# MDR50-Breakout.net
KiCad netlist of a schematic drawn in EAGLE
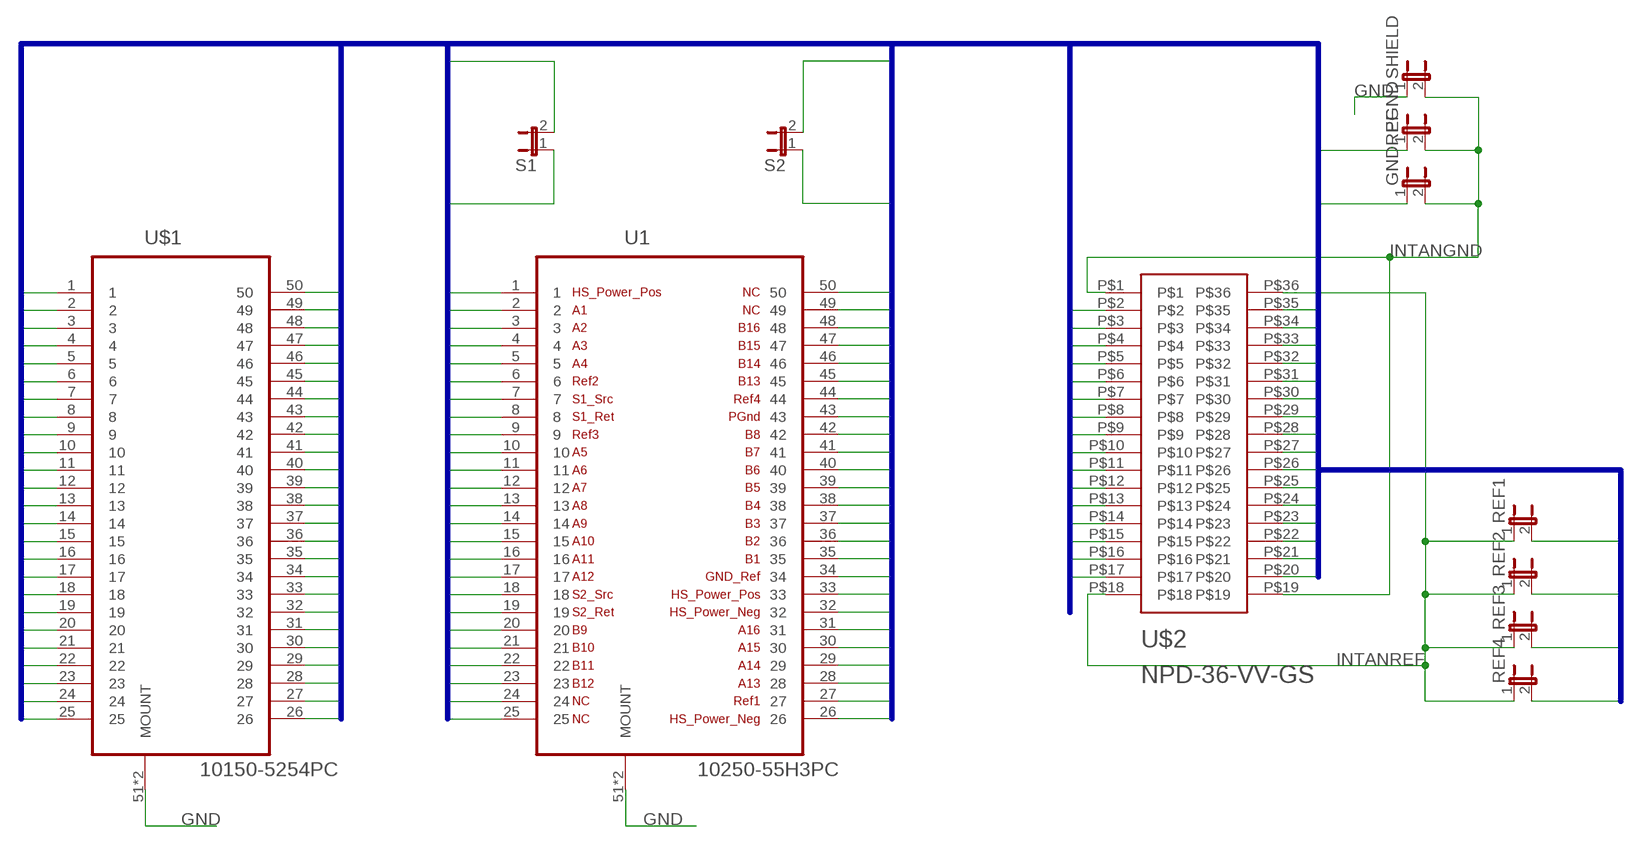
[diagram p0: schematic, sheet 1]

(export (version "E")
  (design (tool "Eeschema 10.0.6"))
  (components
    (comp (ref "GNDREF")
      (value "JUMPER-2PTH")
      (footprint "eagle-import:1X02")
      (libsource (lib "eagle-import") (part "JUMPER-2PTH"))
    )
    (comp (ref "PGND")
      (value "JUMPER-2PTH")
      (footprint "eagle-import:1X02")
      (libsource (lib "eagle-import") (part "JUMPER-2PTH"))
    )
    (comp (ref "REF1")
      (value "JUMPER-2PTH")
      (footprint "eagle-import:1X02")
      (libsource (lib "eagle-import") (part "JUMPER-2PTH"))
    )
    (comp (ref "REF2")
      (value "JUMPER-2PTH")
      (footprint "eagle-import:1X02")
      (libsource (lib "eagle-import") (part "JUMPER-2PTH"))
    )
    (comp (ref "REF3")
      (value "JUMPER-2PTH")
      (footprint "eagle-import:1X02")
      (libsource (lib "eagle-import") (part "JUMPER-2PTH"))
    )
    (comp (ref "REF4")
      (value "JUMPER-2PTH")
      (footprint "eagle-import:1X02")
      (libsource (lib "eagle-import") (part "JUMPER-2PTH"))
    )
    (comp (ref "S1")
      (value "JUMPER-2PTH")
      (footprint "eagle-import:1X02")
      (libsource (lib "eagle-import") (part "JUMPER-2PTH"))
    )
    (comp (ref "S2")
      (value "JUMPER-2PTH")
      (footprint "eagle-import:1X02")
      (libsource (lib "eagle-import") (part "JUMPER-2PTH"))
    )
    (comp (ref "SHIELD")
      (value "JUMPER-2PTH")
      (footprint "eagle-import:1X02")
      (libsource (lib "eagle-import") (part "JUMPER-2PTH"))
    )
    (comp (ref "U$1")
      (value "10150-5254PC")
      (footprint "eagle-import:3M_10150-5242PC")
      (libsource (lib "eagle-import") (part "10150-5254PC"))
    )
    (comp (ref "U$2")
      (value "NPD-36-VV-GS")
      (footprint "eagle-import:NPD-36-VV-GS")
      (libsource (lib "eagle-import") (part "NPD-36-VV-GS"))
    )
    (comp (ref "U1")
      (value "10250-55H3PC")
      (footprint "eagle-import:3M_10250-55H3PC")
      (libsource (lib "eagle-import") (part "10250-55H3PC"))
    )
  )
  (nets
    (net (code "1") (name "/D1") (class "Default")
      (node (ref "U$1") (pin "1") (pinfunction "1_1") (pintype "passive"))
      (node (ref "U1") (pin "1") (pinfunction "1_1") (pintype "passive"))
    )
    (net (code "2") (name "/D2") (class "Default")
      (node (ref "U$1") (pin "2") (pinfunction "2_2") (pintype "passive"))
      (node (ref "U$2") (pin "P$10") (pinfunction "P$10_P$10") (pintype "bidirectional"))
      (node (ref "U1") (pin "2") (pinfunction "2_2") (pintype "passive"))
    )
    (net (code "3") (name "/D3") (class "Default")
      (node (ref "U$1") (pin "3") (pinfunction "3_3") (pintype "passive"))
      (node (ref "U$2") (pin "P$11") (pinfunction "P$11_P$11") (pintype "bidirectional"))
      (node (ref "U1") (pin "3") (pinfunction "3_3") (pintype "passive"))
    )
    (net (code "4") (name "/D4") (class "Default")
      (node (ref "U$1") (pin "4") (pinfunction "4_4") (pintype "passive"))
      (node (ref "U$2") (pin "P$12") (pinfunction "P$12_P$12") (pintype "bidirectional"))
      (node (ref "U1") (pin "4") (pinfunction "4_4") (pintype "passive"))
    )
    (net (code "5") (name "/D5") (class "Default")
      (node (ref "U$1") (pin "5") (pinfunction "5_5") (pintype "passive"))
      (node (ref "U$2") (pin "P$13") (pinfunction "P$13_P$13") (pintype "bidirectional"))
      (node (ref "U1") (pin "5") (pinfunction "5_5") (pintype "passive"))
    )
    (net (code "6") (name "/D6") (class "Default")
      (node (ref "REF2") (pin "2") (pinfunction "2_2") (pintype "passive"))
      (node (ref "U$1") (pin "6") (pinfunction "6_6") (pintype "passive"))
      (node (ref "U1") (pin "6") (pinfunction "6_6") (pintype "passive"))
    )
    (net (code "7") (name "/D7") (class "Default")
      (node (ref "S1") (pin "1") (pinfunction "1_1") (pintype "passive"))
      (node (ref "U$1") (pin "7") (pinfunction "7_7") (pintype "passive"))
      (node (ref "U1") (pin "7") (pinfunction "7_7") (pintype "passive"))
    )
    (net (code "8") (name "/D8") (class "Default")
      (node (ref "S1") (pin "2") (pinfunction "2_2") (pintype "passive"))
      (node (ref "U$1") (pin "8") (pinfunction "8_8") (pintype "passive"))
      (node (ref "U1") (pin "8") (pinfunction "8_8") (pintype "passive"))
    )
    (net (code "9") (name "/D9") (class "Default")
      (node (ref "REF3") (pin "2") (pinfunction "2_2") (pintype "passive"))
      (node (ref "U$1") (pin "9") (pinfunction "9_9") (pintype "passive"))
      (node (ref "U1") (pin "9") (pinfunction "9_9") (pintype "passive"))
    )
    (net (code "10") (name "/D10") (class "Default")
      (node (ref "U$1") (pin "10") (pinfunction "10_10") (pintype "passive"))
      (node (ref "U$2") (pin "P$14") (pinfunction "P$14_P$14") (pintype "bidirectional"))
      (node (ref "U1") (pin "10") (pinfunction "10_10") (pintype "passive"))
    )
    (net (code "11") (name "/D11") (class "Default")
      (node (ref "U$1") (pin "11") (pinfunction "11_11") (pintype "passive"))
      (node (ref "U$2") (pin "P$15") (pinfunction "P$15_P$15") (pintype "bidirectional"))
      (node (ref "U1") (pin "11") (pinfunction "11_11") (pintype "passive"))
    )
    (net (code "12") (name "/D12") (class "Default")
      (node (ref "U$1") (pin "12") (pinfunction "12_12") (pintype "passive"))
      (node (ref "U$2") (pin "P$16") (pinfunction "P$16_P$16") (pintype "bidirectional"))
      (node (ref "U1") (pin "12") (pinfunction "12_12") (pintype "passive"))
    )
    (net (code "13") (name "/D13") (class "Default")
      (node (ref "U$1") (pin "13") (pinfunction "13_13") (pintype "passive"))
      (node (ref "U$2") (pin "P$17") (pinfunction "P$17_P$17") (pintype "bidirectional"))
      (node (ref "U1") (pin "13") (pinfunction "13_13") (pintype "passive"))
    )
    (net (code "14") (name "/D14") (class "Default")
      (node (ref "U$1") (pin "14") (pinfunction "14_14") (pintype "passive"))
      (node (ref "U$2") (pin "P$20") (pinfunction "P$20_P$20") (pintype "bidirectional"))
      (node (ref "U1") (pin "14") (pinfunction "14_14") (pintype "passive"))
    )
    (net (code "15") (name "/D15") (class "Default")
      (node (ref "U$1") (pin "15") (pinfunction "15_15") (pintype "passive"))
      (node (ref "U$2") (pin "P$21") (pinfunction "P$21_P$21") (pintype "bidirectional"))
      (node (ref "U1") (pin "15") (pinfunction "15_15") (pintype "passive"))
    )
    (net (code "16") (name "/D16") (class "Default")
      (node (ref "U$1") (pin "16") (pinfunction "16_16") (pintype "passive"))
      (node (ref "U$2") (pin "P$22") (pinfunction "P$22_P$22") (pintype "bidirectional"))
      (node (ref "U1") (pin "16") (pinfunction "16_16") (pintype "passive"))
    )
    (net (code "17") (name "/D17") (class "Default")
      (node (ref "U$1") (pin "17") (pinfunction "17_17") (pintype "passive"))
      (node (ref "U$2") (pin "P$23") (pinfunction "P$23_P$23") (pintype "bidirectional"))
      (node (ref "U1") (pin "17") (pinfunction "17_17") (pintype "passive"))
    )
    (net (code "18") (name "/D18") (class "Default")
      (node (ref "S2") (pin "1") (pinfunction "1_1") (pintype "passive"))
      (node (ref "U$1") (pin "18") (pinfunction "18_18") (pintype "passive"))
      (node (ref "U1") (pin "18") (pinfunction "18_18") (pintype "passive"))
    )
    (net (code "19") (name "/D19") (class "Default")
      (node (ref "S2") (pin "2") (pinfunction "2_2") (pintype "passive"))
      (node (ref "U$1") (pin "19") (pinfunction "19_19") (pintype "passive"))
      (node (ref "U1") (pin "19") (pinfunction "19_19") (pintype "passive"))
    )
    (net (code "20") (name "/D20") (class "Default")
      (node (ref "U$1") (pin "20") (pinfunction "20_20") (pintype "passive"))
      (node (ref "U$2") (pin "P$2") (pinfunction "P$2_P$2") (pintype "bidirectional"))
      (node (ref "U1") (pin "20") (pinfunction "20_20") (pintype "passive"))
    )
    (net (code "21") (name "/D21") (class "Default")
      (node (ref "U$1") (pin "21") (pinfunction "21_21") (pintype "passive"))
      (node (ref "U$2") (pin "P$3") (pinfunction "P$3_P$3") (pintype "bidirectional"))
      (node (ref "U1") (pin "21") (pinfunction "21_21") (pintype "passive"))
    )
    (net (code "22") (name "/D22") (class "Default")
      (node (ref "U$1") (pin "22") (pinfunction "22_22") (pintype "passive"))
      (node (ref "U$2") (pin "P$4") (pinfunction "P$4_P$4") (pintype "bidirectional"))
      (node (ref "U1") (pin "22") (pinfunction "22_22") (pintype "passive"))
    )
    (net (code "23") (name "/D23") (class "Default")
      (node (ref "U$1") (pin "23") (pinfunction "23_23") (pintype "passive"))
      (node (ref "U$2") (pin "P$5") (pinfunction "P$5_P$5") (pintype "bidirectional"))
      (node (ref "U1") (pin "23") (pinfunction "23_23") (pintype "passive"))
    )
    (net (code "24") (name "/D24") (class "Default")
      (node (ref "U$1") (pin "24") (pinfunction "24_24") (pintype "passive"))
      (node (ref "U1") (pin "24") (pinfunction "24_24") (pintype "passive"))
    )
    (net (code "25") (name "/D25") (class "Default")
      (node (ref "U$1") (pin "25") (pinfunction "25_25") (pintype "passive"))
      (node (ref "U1") (pin "25") (pinfunction "25_25") (pintype "passive"))
    )
    (net (code "26") (name "/D26") (class "Default")
      (node (ref "U$1") (pin "26") (pinfunction "26_26") (pintype "passive"))
      (node (ref "U1") (pin "26") (pinfunction "26_26") (pintype "passive"))
    )
    (net (code "27") (name "/D27") (class "Default")
      (node (ref "REF1") (pin "2") (pinfunction "2_2") (pintype "passive"))
      (node (ref "U$1") (pin "27") (pinfunction "27_27") (pintype "passive"))
      (node (ref "U1") (pin "27") (pinfunction "27_27") (pintype "passive"))
    )
    (net (code "28") (name "/D28") (class "Default")
      (node (ref "U$1") (pin "28") (pinfunction "28_28") (pintype "passive"))
      (node (ref "U$2") (pin "P$24") (pinfunction "P$24_P$24") (pintype "bidirectional"))
      (node (ref "U1") (pin "28") (pinfunction "28_28") (pintype "passive"))
    )
    (net (code "29") (name "/D29") (class "Default")
      (node (ref "U$1") (pin "29") (pinfunction "29_29") (pintype "passive"))
      (node (ref "U$2") (pin "P$25") (pinfunction "P$25_P$25") (pintype "bidirectional"))
      (node (ref "U1") (pin "29") (pinfunction "29_29") (pintype "passive"))
    )
    (net (code "30") (name "/D30") (class "Default")
      (node (ref "U$1") (pin "30") (pinfunction "30_30") (pintype "passive"))
      (node (ref "U$2") (pin "P$26") (pinfunction "P$26_P$26") (pintype "bidirectional"))
      (node (ref "U1") (pin "30") (pinfunction "30_30") (pintype "passive"))
    )
    (net (code "31") (name "/D31") (class "Default")
      (node (ref "U$1") (pin "31") (pinfunction "31_31") (pintype "passive"))
      (node (ref "U$2") (pin "P$27") (pinfunction "P$27_P$27") (pintype "bidirectional"))
      (node (ref "U1") (pin "31") (pinfunction "31_31") (pintype "passive"))
    )
    (net (code "32") (name "/D32") (class "Default")
      (node (ref "U$1") (pin "32") (pinfunction "32_32") (pintype "passive"))
      (node (ref "U1") (pin "32") (pinfunction "32_32") (pintype "passive"))
    )
    (net (code "33") (name "/D33") (class "Default")
      (node (ref "U$1") (pin "33") (pinfunction "33_33") (pintype "passive"))
      (node (ref "U1") (pin "33") (pinfunction "33_33") (pintype "passive"))
    )
    (net (code "34") (name "/D34") (class "Default")
      (node (ref "GNDREF") (pin "1") (pinfunction "1_1") (pintype "passive"))
      (node (ref "U$1") (pin "34") (pinfunction "34_34") (pintype "passive"))
      (node (ref "U1") (pin "34") (pinfunction "34_34") (pintype "passive"))
    )
    (net (code "35") (name "/D35") (class "Default")
      (node (ref "U$1") (pin "35") (pinfunction "35_35") (pintype "passive"))
      (node (ref "U$2") (pin "P$28") (pinfunction "P$28_P$28") (pintype "bidirectional"))
      (node (ref "U1") (pin "35") (pinfunction "35_35") (pintype "passive"))
    )
    (net (code "36") (name "/D36") (class "Default")
      (node (ref "U$1") (pin "36") (pinfunction "36_36") (pintype "passive"))
      (node (ref "U$2") (pin "P$29") (pinfunction "P$29_P$29") (pintype "bidirectional"))
      (node (ref "U1") (pin "36") (pinfunction "36_36") (pintype "passive"))
    )
    (net (code "37") (name "/D37") (class "Default")
      (node (ref "U$1") (pin "37") (pinfunction "37_37") (pintype "passive"))
      (node (ref "U$2") (pin "P$30") (pinfunction "P$30_P$30") (pintype "bidirectional"))
      (node (ref "U1") (pin "37") (pinfunction "37_37") (pintype "passive"))
    )
    (net (code "38") (name "/D38") (class "Default")
      (node (ref "U$1") (pin "38") (pinfunction "38_38") (pintype "passive"))
      (node (ref "U$2") (pin "P$31") (pinfunction "P$31_P$31") (pintype "bidirectional"))
      (node (ref "U1") (pin "38") (pinfunction "38_38") (pintype "passive"))
    )
    (net (code "39") (name "/D39") (class "Default")
      (node (ref "U$1") (pin "39") (pinfunction "39_39") (pintype "passive"))
      (node (ref "U$2") (pin "P$32") (pinfunction "P$32_P$32") (pintype "bidirectional"))
      (node (ref "U1") (pin "39") (pinfunction "39_39") (pintype "passive"))
    )
    (net (code "40") (name "/D40") (class "Default")
      (node (ref "U$1") (pin "40") (pinfunction "40_40") (pintype "passive"))
      (node (ref "U$2") (pin "P$33") (pinfunction "P$33_P$33") (pintype "bidirectional"))
      (node (ref "U1") (pin "40") (pinfunction "40_40") (pintype "passive"))
    )
    (net (code "41") (name "/D41") (class "Default")
      (node (ref "U$1") (pin "41") (pinfunction "41_41") (pintype "passive"))
      (node (ref "U$2") (pin "P$34") (pinfunction "P$34_P$34") (pintype "bidirectional"))
      (node (ref "U1") (pin "41") (pinfunction "41_41") (pintype "passive"))
    )
    (net (code "42") (name "/D42") (class "Default")
      (node (ref "U$1") (pin "42") (pinfunction "42_42") (pintype "passive"))
      (node (ref "U$2") (pin "P$35") (pinfunction "P$35_P$35") (pintype "bidirectional"))
      (node (ref "U1") (pin "42") (pinfunction "42_42") (pintype "passive"))
    )
    (net (code "43") (name "/D43") (class "Default")
      (node (ref "PGND") (pin "1") (pinfunction "1_1") (pintype "passive"))
      (node (ref "U$1") (pin "43") (pinfunction "43_43") (pintype "passive"))
      (node (ref "U1") (pin "43") (pinfunction "43_43") (pintype "passive"))
    )
    (net (code "44") (name "/D44") (class "Default")
      (node (ref "REF4") (pin "2") (pinfunction "2_2") (pintype "passive"))
      (node (ref "U$1") (pin "44") (pinfunction "44_44") (pintype "passive"))
      (node (ref "U1") (pin "44") (pinfunction "44_44") (pintype "passive"))
    )
    (net (code "45") (name "/D45") (class "Default")
      (node (ref "U$1") (pin "45") (pinfunction "45_45") (pintype "passive"))
      (node (ref "U$2") (pin "P$6") (pinfunction "P$6_P$6") (pintype "bidirectional"))
      (node (ref "U1") (pin "45") (pinfunction "45_45") (pintype "passive"))
    )
    (net (code "46") (name "/D46") (class "Default")
      (node (ref "U$1") (pin "46") (pinfunction "46_46") (pintype "passive"))
      (node (ref "U$2") (pin "P$7") (pinfunction "P$7_P$7") (pintype "bidirectional"))
      (node (ref "U1") (pin "46") (pinfunction "46_46") (pintype "passive"))
    )
    (net (code "47") (name "/D47") (class "Default")
      (node (ref "U$1") (pin "47") (pinfunction "47_47") (pintype "passive"))
      (node (ref "U$2") (pin "P$8") (pinfunction "P$8_P$8") (pintype "bidirectional"))
      (node (ref "U1") (pin "47") (pinfunction "47_47") (pintype "passive"))
    )
    (net (code "48") (name "/D48") (class "Default")
      (node (ref "U$1") (pin "48") (pinfunction "48_48") (pintype "passive"))
      (node (ref "U$2") (pin "P$9") (pinfunction "P$9_P$9") (pintype "bidirectional"))
      (node (ref "U1") (pin "48") (pinfunction "48_48") (pintype "passive"))
    )
    (net (code "49") (name "/D49") (class "Default")
      (node (ref "U$1") (pin "49") (pinfunction "49_49") (pintype "passive"))
      (node (ref "U1") (pin "49") (pinfunction "49_49") (pintype "passive"))
    )
    (net (code "50") (name "/D50") (class "Default")
      (node (ref "U$1") (pin "50") (pinfunction "50_50") (pintype "passive"))
      (node (ref "U1") (pin "50") (pinfunction "50_50") (pintype "passive"))
    )
    (net (code "51") (name "/GND") (class "Default")
      (node (ref "SHIELD") (pin "1") (pinfunction "1_1") (pintype "passive"))
      (node (ref "U$1") (pin "51") (pinfunction "MOUNT_51") (pintype "bidirectional"))
      (node (ref "U$1") (pin "52") (pinfunction "MOUNT_52") (pintype "bidirectional"))
      (node (ref "U1") (pin "51") (pinfunction "MOUNT_51") (pintype "bidirectional"))
      (node (ref "U1") (pin "52") (pinfunction "MOUNT_52") (pintype "bidirectional"))
    )
    (net (code "52") (name "/INTANGND") (class "Default")
      (node (ref "GNDREF") (pin "2") (pinfunction "2_2") (pintype "passive"))
      (node (ref "PGND") (pin "2") (pinfunction "2_2") (pintype "passive"))
      (node (ref "SHIELD") (pin "2") (pinfunction "2_2") (pintype "passive"))
      (node (ref "U$2") (pin "P$1") (pinfunction "P$1_P$1") (pintype "bidirectional"))
      (node (ref "U$2") (pin "P$19") (pinfunction "P$19_P$19") (pintype "bidirectional"))
    )
    (net (code "53") (name "/INTANREF") (class "Default")
      (node (ref "REF1") (pin "1") (pinfunction "1_1") (pintype "passive"))
      (node (ref "REF2") (pin "1") (pinfunction "1_1") (pintype "passive"))
      (node (ref "REF3") (pin "1") (pinfunction "1_1") (pintype "passive"))
      (node (ref "REF4") (pin "1") (pinfunction "1_1") (pintype "passive"))
      (node (ref "U$2") (pin "P$18") (pinfunction "P$18_P$18") (pintype "bidirectional"))
      (node (ref "U$2") (pin "P$36") (pinfunction "P$36_P$36") (pintype "bidirectional"))
    )
  )
)
